# 03_Schematic.net
KiCad netlist of a schematic drawn in Altium Designer
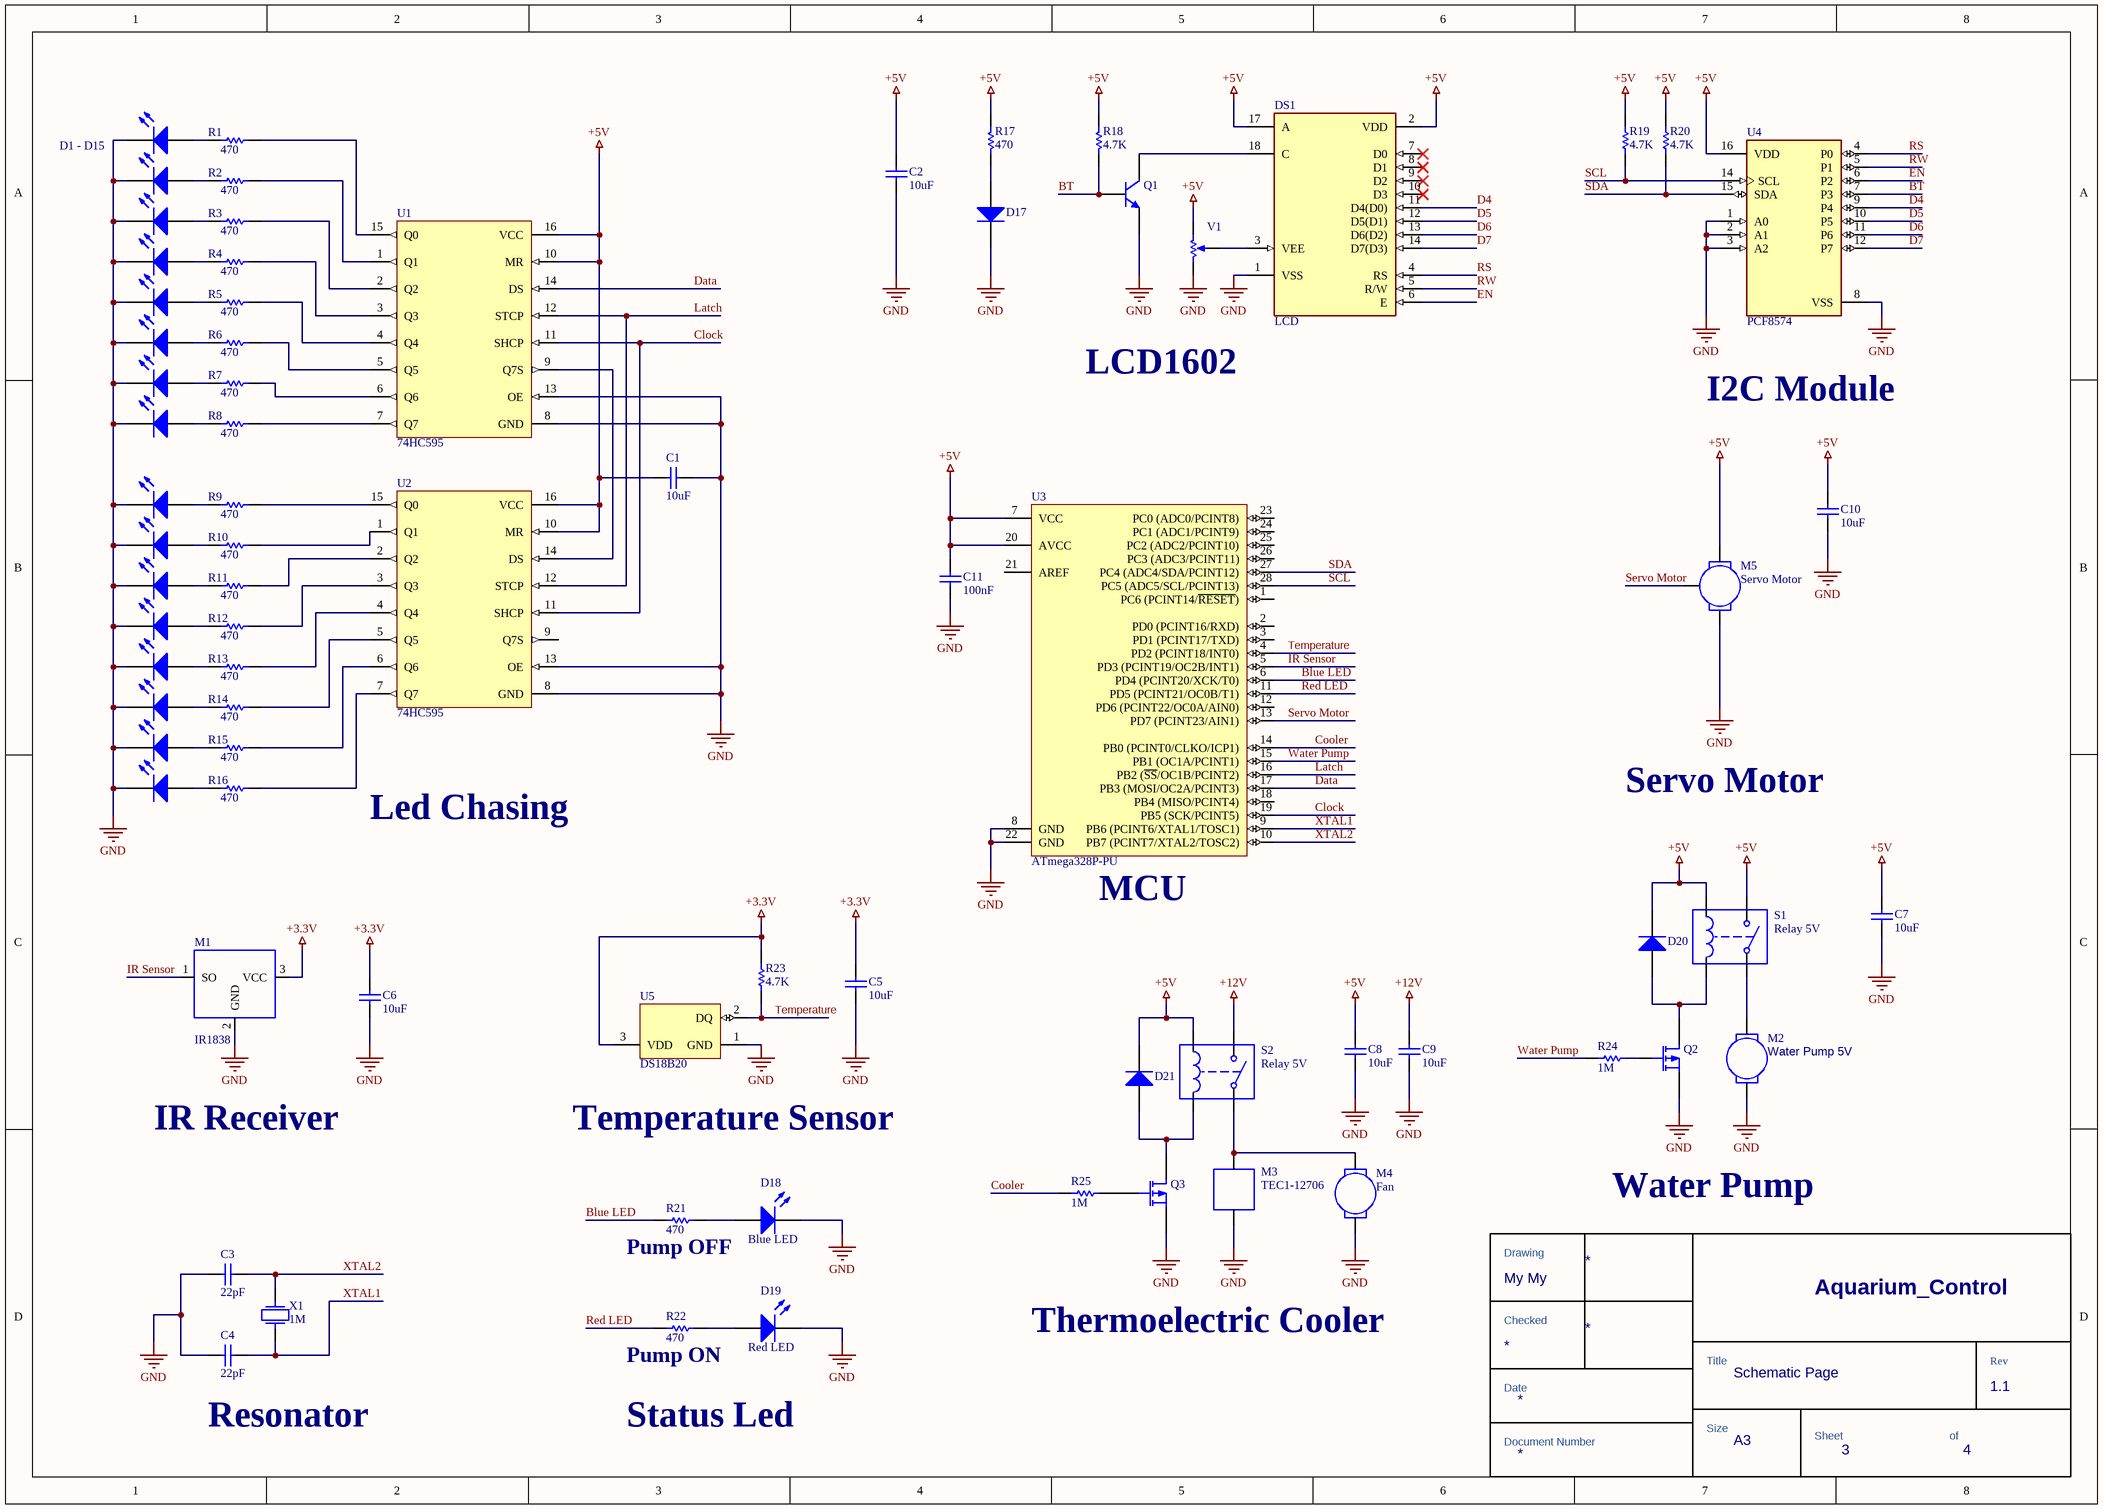
[diagram p0: 03.Schematic.SchDoc]

(export (version "E")
  (design (tool "Eeschema 10.0.6"))
  (components
    (comp (ref "*")
      (value "TitleBlock")
      (description "Common Title Block")
      (libsource (lib "Aquarium_Control") (part "TitleBlock"))
    )
    (comp (ref "C1")
      (value "10uF")
      (description "Capacitor")
      (libsource (lib "Simulation Generic Components") (part "Capacitor"))
    )
    (comp (ref "C2")
      (value "10uF")
      (description "Capacitor")
      (libsource (lib "Simulation Generic Components") (part "Capacitor"))
    )
    (comp (ref "C3")
      (value "22pF")
      (description "Capacitor")
      (libsource (lib "Simulation Generic Components") (part "Capacitor"))
    )
    (comp (ref "C4")
      (value "22pF")
      (description "Capacitor")
      (libsource (lib "Simulation Generic Components") (part "Capacitor"))
    )
    (comp (ref "C5")
      (value "10uF")
      (description "Capacitor")
      (libsource (lib "Simulation Generic Components") (part "Capacitor"))
    )
    (comp (ref "C6")
      (value "10uF")
      (description "Capacitor")
      (libsource (lib "Simulation Generic Components") (part "Capacitor"))
    )
    (comp (ref "C7")
      (value "10uF")
      (description "Capacitor")
      (libsource (lib "Simulation Generic Components") (part "Capacitor"))
    )
    (comp (ref "C8")
      (value "10uF")
      (description "Capacitor")
      (libsource (lib "Simulation Generic Components") (part "Capacitor"))
    )
    (comp (ref "C9")
      (value "10uF")
      (description "Capacitor")
      (libsource (lib "Simulation Generic Components") (part "Capacitor"))
    )
    (comp (ref "C10")
      (value "10uF")
      (description "Capacitor")
      (libsource (lib "Simulation Generic Components") (part "Capacitor"))
    )
    (comp (ref "C11")
      (value "100nF")
      (description "Capacitor")
      (libsource (lib "Simulation Generic Components") (part "Capacitor"))
    )
    (comp (ref "D1")
      (value "Light-Emitting Diode")
      (libsource (lib "Simulation Generic Components") (part "LED"))
    )
    (comp (ref "D2")
      (value "Light-Emitting Diode")
      (libsource (lib "Simulation Generic Components") (part "LED"))
    )
    (comp (ref "D3")
      (value "Light-Emitting Diode")
      (libsource (lib "Simulation Generic Components") (part "LED"))
    )
    (comp (ref "D4")
      (value "Light-Emitting Diode")
      (libsource (lib "Simulation Generic Components") (part "LED"))
    )
    (comp (ref "D5")
      (value "Light-Emitting Diode")
      (libsource (lib "Simulation Generic Components") (part "LED"))
    )
    (comp (ref "D6")
      (value "Light-Emitting Diode")
      (libsource (lib "Simulation Generic Components") (part "LED"))
    )
    (comp (ref "D7")
      (value "Light-Emitting Diode")
      (libsource (lib "Simulation Generic Components") (part "LED"))
    )
    (comp (ref "D8")
      (value "Light-Emitting Diode")
      (libsource (lib "Simulation Generic Components") (part "LED"))
    )
    (comp (ref "D9")
      (value "Light-Emitting Diode")
      (libsource (lib "Simulation Generic Components") (part "LED"))
    )
    (comp (ref "D10")
      (value "Light-Emitting Diode")
      (libsource (lib "Simulation Generic Components") (part "LED"))
    )
    (comp (ref "D11")
      (value "Light-Emitting Diode")
      (libsource (lib "Simulation Generic Components") (part "LED"))
    )
    (comp (ref "D12")
      (value "Light-Emitting Diode")
      (libsource (lib "Simulation Generic Components") (part "LED"))
    )
    (comp (ref "D13")
      (value "Light-Emitting Diode")
      (libsource (lib "Simulation Generic Components") (part "LED"))
    )
    (comp (ref "D14")
      (value "Light-Emitting Diode")
      (libsource (lib "Simulation Generic Components") (part "LED"))
    )
    (comp (ref "D15")
      (value "Light-Emitting Diode")
      (libsource (lib "Simulation Generic Components") (part "LED"))
    )
    (comp (ref "D16")
      (value "Light-Emitting Diode")
      (libsource (lib "Simulation Generic Components") (part "LED"))
    )
    (comp (ref "D17") (value "Diode") (libsource (lib "Simulation Generic Components") (part "Diode")))
    (comp (ref "D18")
      (value "Blue LED")
      (description "Light-Emitting Diode")
      (libsource (lib "Simulation Generic Components") (part "LED"))
    )
    (comp (ref "D19")
      (value "Red LED")
      (description "Light-Emitting Diode")
      (libsource (lib "Simulation Generic Components") (part "LED"))
    )
    (comp (ref "D20") (value "Diode") (libsource (lib "Simulation Generic Components") (part "Diode")))
    (comp (ref "D21") (value "Diode") (libsource (lib "Simulation Generic Components") (part "Diode")))
    (comp (ref "DS1")
      (value "LCD")
      (footprint "FP-EA_DIP162-DHNLED-MFG")
      (description "LCD MOD CHAR 2X16 Y/G BACKLIT")
      (fields
        (field (name "MANUFACTURER PART NUMBER") "EA DIP162-DHNLED")
        (field (name "MANUFACTURER") "Display Visions")
      )
      (libsource (lib "Altium Content Vault") (part "d15ad439837a3ed901fb7cfc26901aa"))
    )
    (comp (ref "M1") (value "IR1838") (libsource (lib "Aquarium_Control") (part "IR1838")))
    (comp (ref "M2")
      (value "Water Pump 5V")
      (description "DC Motor")
      (libsource (lib "Aquarium_Control_1") (part "DC Motor"))
    )
    (comp (ref "M3") (value "TEC1-12706") (libsource (lib "Aquarium_Control") (part "TEC1-12706")))
    (comp (ref "M4") (value "Fan") (libsource (lib "Aquarium_Control") (part "Fan")))
    (comp (ref "M5") (value "Servo Motor") (libsource (lib "Aquarium_Control") (part "Servo Motor")))
    (comp (ref "Q1")
      (value "Bipolar NPN 3 Pins Transistor VBIC Model")
      (libsource (lib "Simulation Generic Components") (part "BJT NPN VBIC"))
    )
    (comp (ref "Q2")
      (value "P-channel Power MOSFET VDMOS Model")
      (libsource (lib "Simulation Generic Components") (part "MOSFET P-ch VDMOS"))
    )
    (comp (ref "Q3")
      (value "P-channel Power MOSFET VDMOS Model")
      (libsource (lib "Simulation Generic Components") (part "MOSFET P-ch VDMOS"))
    )
    (comp (ref "R1")
      (value "470")
      (description "Resistor")
      (libsource (lib "Simulation Generic Components") (part "Resistor"))
    )
    (comp (ref "R2")
      (value "470")
      (description "Resistor")
      (libsource (lib "Simulation Generic Components") (part "Resistor"))
    )
    (comp (ref "R3")
      (value "470")
      (description "Resistor")
      (libsource (lib "Simulation Generic Components") (part "Resistor"))
    )
    (comp (ref "R4")
      (value "470")
      (description "Resistor")
      (libsource (lib "Simulation Generic Components") (part "Resistor"))
    )
    (comp (ref "R5")
      (value "470")
      (description "Resistor")
      (libsource (lib "Simulation Generic Components") (part "Resistor"))
    )
    (comp (ref "R6")
      (value "470")
      (description "Resistor")
      (libsource (lib "Simulation Generic Components") (part "Resistor"))
    )
    (comp (ref "R7")
      (value "470")
      (description "Resistor")
      (libsource (lib "Simulation Generic Components") (part "Resistor"))
    )
    (comp (ref "R8")
      (value "470")
      (description "Resistor")
      (libsource (lib "Simulation Generic Components") (part "Resistor"))
    )
    (comp (ref "R9")
      (value "470")
      (description "Resistor")
      (libsource (lib "Simulation Generic Components") (part "Resistor"))
    )
    (comp (ref "R10")
      (value "470")
      (description "Resistor")
      (libsource (lib "Simulation Generic Components") (part "Resistor"))
    )
    (comp (ref "R11")
      (value "470")
      (description "Resistor")
      (libsource (lib "Simulation Generic Components") (part "Resistor"))
    )
    (comp (ref "R12")
      (value "470")
      (description "Resistor")
      (libsource (lib "Simulation Generic Components") (part "Resistor"))
    )
    (comp (ref "R13")
      (value "470")
      (description "Resistor")
      (libsource (lib "Simulation Generic Components") (part "Resistor"))
    )
    (comp (ref "R14")
      (value "470")
      (description "Resistor")
      (libsource (lib "Simulation Generic Components") (part "Resistor"))
    )
    (comp (ref "R15")
      (value "470")
      (description "Resistor")
      (libsource (lib "Simulation Generic Components") (part "Resistor"))
    )
    (comp (ref "R16")
      (value "470")
      (description "Resistor")
      (libsource (lib "Simulation Generic Components") (part "Resistor"))
    )
    (comp (ref "R17")
      (value "470")
      (description "Resistor")
      (libsource (lib "Simulation Generic Components") (part "Resistor"))
    )
    (comp (ref "R18")
      (value "4.7K")
      (description "Resistor")
      (libsource (lib "Simulation Generic Components") (part "Resistor"))
    )
    (comp (ref "R19")
      (value "4.7K")
      (description "Resistor")
      (libsource (lib "Simulation Generic Components") (part "Resistor"))
    )
    (comp (ref "R20")
      (value "4.7K")
      (description "Resistor")
      (libsource (lib "Simulation Generic Components") (part "Resistor"))
    )
    (comp (ref "R21")
      (value "470")
      (description "Resistor")
      (libsource (lib "Simulation Generic Components") (part "Resistor"))
    )
    (comp (ref "R22")
      (value "470")
      (description "Resistor")
      (libsource (lib "Simulation Generic Components") (part "Resistor"))
    )
    (comp (ref "R23")
      (value "4.7K")
      (description "Resistor")
      (libsource (lib "Simulation Generic Components") (part "Resistor"))
    )
    (comp (ref "R24")
      (value "1M")
      (description "Resistor")
      (libsource (lib "Simulation Generic Components") (part "Resistor"))
    )
    (comp (ref "R25")
      (value "1M")
      (description "Resistor")
      (libsource (lib "Simulation Generic Components") (part "Resistor"))
    )
    (comp (ref "S1")
      (value "Relay 5V")
      (description "Single-Pole, Single-Throw Normally Opened Relay")
      (libsource (lib "Simulation Generic Components") (part "SPST Relay NO"))
    )
    (comp (ref "S2")
      (value "Single-Pole, Single-Throw Normally Opened Relay")
      (libsource (lib "Simulation Generic Components") (part "SPST Relay NO"))
    )
    (comp (ref "U1") (value "74HC595") (libsource (lib "Aquarium_Control") (part "74HC595")))
    (comp (ref "U2") (value "74HC595") (libsource (lib "Aquarium_Control") (part "74HC595")))
    (comp (ref "U3")
      (value "ATmega328P-PU")
      (footprint "28P3")
      (libsource (lib "Altium Content Vault") (part "MC-8B-ATM48-IL28"))
    )
    (comp (ref "U4")
      (value "PCF8574")
      (footprint "FP-SOT162-1-MFG")
      (description "IC I/O EXPANDER I2C 8B 16SOIC")
      (fields
        (field (name "MANUFACTURER PART NUMBER") "PCF8574T/3,518")
        (field (name "MANUFACTURER") "NXP Semiconductors")
      )
      (libsource (lib "Altium Content Vault") (part "f7fde53ce59de981fb0b266a4e103eb"))
    )
    (comp (ref "U5")
      (value "DS18B20")
      (footprint "Q3+1")
      (libsource (lib "Altium Content Vault") (part "SEN-TEMP-DS1821-SIL3"))
    )
    (comp (ref "V1")
      (value "Potentiometer")
      (libsource (lib "Simulation Generic Components") (part "Potentiometer"))
    )
    (comp (ref "X1")
      (value "Crystal")
      (fields (field (name "F0") "1M"))
      (libsource (lib "Simulation Generic Components") (part "Crystal"))
    )
  )
  (nets
    (net (code "1") (name "+3.3V") (class "Default")
      (node (ref "C5") (pin "2") (pinfunction "2_2") (pintype "passive"))
      (node (ref "C6") (pin "2") (pinfunction "2_2") (pintype "passive"))
      (node (ref "M1") (pin "3") (pinfunction "VCC_3") (pintype "passive"))
      (node (ref "R23") (pin "2") (pinfunction "2_2") (pintype "passive"))
      (node (ref "U5") (pin "3") (pinfunction "VDD_3") (pintype "power_in"))
    )
    (net (code "2") (name "+5V") (class "Default")
      (node (ref "C1") (pin "1") (pinfunction "1_1") (pintype "passive"))
      (node (ref "C10") (pin "2") (pinfunction "2_2") (pintype "passive"))
      (node (ref "C11") (pin "2") (pinfunction "2_2") (pintype "passive"))
      (node (ref "C2") (pin "2") (pinfunction "2_2") (pintype "passive"))
      (node (ref "C7") (pin "2") (pinfunction "2_2") (pintype "passive"))
      (node (ref "C8") (pin "2") (pinfunction "2_2") (pintype "passive"))
      (node (ref "D20") (pin "2") (pinfunction "K_2") (pintype "passive"))
      (node (ref "D21") (pin "2") (pinfunction "K_2") (pintype "passive"))
      (node (ref "DS1") (pin "17") (pinfunction "A_17") (pintype "passive"))
      (node (ref "DS1") (pin "2") (pinfunction "VDD_2") (pintype "power_in"))
      (node (ref "M5") (pin "1") (pinfunction "1_1") (pintype "passive"))
      (node (ref "R17") (pin "2") (pinfunction "2_2") (pintype "passive"))
      (node (ref "R18") (pin "2") (pinfunction "2_2") (pintype "passive"))
      (node (ref "R19") (pin "2") (pinfunction "2_2") (pintype "passive"))
      (node (ref "R20") (pin "2") (pinfunction "2_2") (pintype "passive"))
      (node (ref "S1") (pin "2") (pinfunction "2_2") (pintype "passive"))
      (node (ref "S1") (pin "4") (pinfunction "4_4") (pintype "passive"))
      (node (ref "S2") (pin "4") (pinfunction "4_4") (pintype "passive"))
      (node (ref "U1") (pin "10") (pinfunction "MR_10") (pintype "input"))
      (node (ref "U1") (pin "16") (pinfunction "VCC_16") (pintype "passive"))
      (node (ref "U2") (pin "10") (pinfunction "MR_10") (pintype "input"))
      (node (ref "U2") (pin "16") (pinfunction "VCC_16") (pintype "passive"))
      (node (ref "U3") (pin "20") (pinfunction "AVCC_20") (pintype "power_in"))
      (node (ref "U3") (pin "7") (pinfunction "VCC_7") (pintype "power_in"))
      (node (ref "U4") (pin "16") (pinfunction "VDD_16") (pintype "power_in"))
      (node (ref "V1") (pin "1") (pinfunction "TOP_1") (pintype "passive"))
    )
    (net (code "3") (name "+12V") (class "Default")
      (node (ref "C9") (pin "2") (pinfunction "2_2") (pintype "passive"))
      (node (ref "S2") (pin "2") (pinfunction "2_2") (pintype "passive"))
    )
    (net (code "4") (name "/BT") (class "Default")
      (node (ref "Q1") (pin "2") (pinfunction "B_2") (pintype "passive"))
      (node (ref "R18") (pin "1") (pinfunction "1_1") (pintype "passive"))
      (node (ref "U4") (pin "7") (pinfunction "P3_7") (pintype "bidirectional"))
    )
    (net (code "5") (name "/Blue LED") (class "Default")
      (node (ref "R21") (pin "1") (pinfunction "1_1") (pintype "passive"))
      (node (ref "U3") (pin "6") (pinfunction "PD4_(PCINT20/XCK/T0)_6") (pintype "bidirectional"))
    )
    (net (code "6") (name "/Clock") (class "Default")
      (node (ref "U1") (pin "11") (pinfunction "SHCP_11") (pintype "input"))
      (node (ref "U2") (pin "11") (pinfunction "SHCP_11") (pintype "input"))
      (node (ref "U3") (pin "19") (pinfunction "PB5_(SCK/PCINT5)_19") (pintype "bidirectional"))
    )
    (net (code "7") (name "/Cooler") (class "Default")
      (node (ref "R25") (pin "1") (pinfunction "1_1") (pintype "passive"))
      (node (ref "U3") (pin "14") (pinfunction "PB0_(PCINT0/CLKO/ICP1)_14") (pintype "bidirectional"))
    )
    (net (code "8") (name "/D4") (class "Default")
      (node (ref "DS1") (pin "11") (pinfunction "D4(D0)_11") (pintype "input"))
      (node (ref "U4") (pin "9") (pinfunction "P4_9") (pintype "bidirectional"))
    )
    (net (code "9") (name "/D5") (class "Default")
      (node (ref "DS1") (pin "12") (pinfunction "D5(D1)_12") (pintype "input"))
      (node (ref "U4") (pin "10") (pinfunction "P5_10") (pintype "bidirectional"))
    )
    (net (code "10") (name "/D6") (class "Default")
      (node (ref "DS1") (pin "13") (pinfunction "D6(D2)_13") (pintype "input"))
      (node (ref "U4") (pin "11") (pinfunction "P6_11") (pintype "bidirectional"))
    )
    (net (code "11") (name "/D7") (class "Default")
      (node (ref "DS1") (pin "14") (pinfunction "D7(D3)_14") (pintype "input"))
      (node (ref "U4") (pin "12") (pinfunction "P7_12") (pintype "bidirectional"))
    )
    (net (code "12") (name "/Data") (class "Default")
      (node (ref "U1") (pin "14") (pinfunction "DS_14") (pintype "input"))
      (node (ref "U3") (pin "17") (pinfunction "PB3_(MOSI/OC2A/PCINT3)_17") (pintype "bidirectional"))
    )
    (net (code "13") (name "/EN") (class "Default")
      (node (ref "DS1") (pin "6") (pinfunction "E_6") (pintype "input"))
      (node (ref "U4") (pin "6") (pinfunction "P2_6") (pintype "bidirectional"))
    )
    (net (code "14") (name "/IR Sensor") (class "Default")
      (node (ref "M1") (pin "1") (pinfunction "SO_1") (pintype "passive"))
      (node (ref "U3") (pin "5") (pinfunction "PD3_(PCINT19/OC2B/INT1)_5") (pintype "bidirectional"))
    )
    (net (code "15") (name "/Latch") (class "Default")
      (node (ref "U1") (pin "12") (pinfunction "STCP_12") (pintype "input"))
      (node (ref "U2") (pin "12") (pinfunction "STCP_12") (pintype "input"))
      (node (ref "U3") (pin "16") (pinfunction "PB2_(~{SS}/OC1B/PCINT2)_16") (pintype "bidirectional"))
    )
    (net (code "16") (name "/RS") (class "Default")
      (node (ref "DS1") (pin "4") (pinfunction "RS_4") (pintype "input"))
      (node (ref "U4") (pin "4") (pinfunction "P0_4") (pintype "bidirectional"))
    )
    (net (code "17") (name "/RW") (class "Default")
      (node (ref "DS1") (pin "5") (pinfunction "R/W_5") (pintype "input"))
      (node (ref "U4") (pin "5") (pinfunction "P1_5") (pintype "bidirectional"))
    )
    (net (code "18") (name "/Red LED") (class "Default")
      (node (ref "R22") (pin "1") (pinfunction "1_1") (pintype "passive"))
      (node (ref "U3") (pin "11") (pinfunction "PD5_(PCINT21/OC0B/T1)_11") (pintype "bidirectional"))
    )
    (net (code "19") (name "/SCL") (class "Default")
      (node (ref "R19") (pin "1") (pinfunction "1_1") (pintype "passive"))
      (node (ref "U3") (pin "28") (pinfunction "PC5_(ADC5/SCL/PCINT13)_28") (pintype "bidirectional"))
      (node (ref "U4") (pin "14") (pinfunction "SCL_14") (pintype "input"))
    )
    (net (code "20") (name "/SDA") (class "Default")
      (node (ref "R20") (pin "1") (pinfunction "1_1") (pintype "passive"))
      (node (ref "U3") (pin "27") (pinfunction "PC4_(ADC4/SDA/PCINT12)_27") (pintype "bidirectional"))
      (node (ref "U4") (pin "15") (pinfunction "SDA_15") (pintype "bidirectional"))
    )
    (net (code "21") (name "/Servo Motor") (class "Default")
      (node (ref "M5") (pin "1") (pinfunction "1_1") (pintype "passive"))
      (node (ref "U3") (pin "13") (pinfunction "PD7_(PCINT23/AIN1)_13") (pintype "bidirectional"))
    )
    (net (code "22") (name "/Temperature") (class "Default")
      (node (ref "R23") (pin "1") (pinfunction "1_1") (pintype "passive"))
      (node (ref "U3") (pin "4") (pinfunction "PD2_(PCINT18/INT0)_4") (pintype "bidirectional"))
      (node (ref "U5") (pin "2") (pinfunction "DQ_2") (pintype "bidirectional"))
    )
    (net (code "23") (name "/Water Pump") (class "Default")
      (node (ref "R24") (pin "1") (pinfunction "1_1") (pintype "passive"))
      (node (ref "U3") (pin "15") (pinfunction "PB1_(OC1A/PCINT1)_15") (pintype "bidirectional"))
    )
    (net (code "24") (name "/XTAL1") (class "Default")
      (node (ref "C4") (pin "2") (pinfunction "2_2") (pintype "passive"))
      (node (ref "U3") (pin "9") (pinfunction "PB6_(PCINT6/XTAL1/TOSC1)_9") (pintype "bidirectional"))
      (node (ref "X1") (pin "1") (pinfunction "1_1") (pintype "passive"))
    )
    (net (code "25") (name "/XTAL2") (class "Default")
      (node (ref "C3") (pin "2") (pinfunction "2_2") (pintype "passive"))
      (node (ref "U3") (pin "10") (pinfunction "PB7_(PCINT7/XTAL2/TOSC2)_10") (pintype "bidirectional"))
      (node (ref "X1") (pin "2") (pinfunction "2_2") (pintype "passive"))
    )
    (net (code "26") (name "GND") (class "Default")
      (node (ref "C1") (pin "2") (pinfunction "2_2") (pintype "passive"))
      (node (ref "C10") (pin "1") (pinfunction "1_1") (pintype "passive"))
      (node (ref "C11") (pin "1") (pinfunction "1_1") (pintype "passive"))
      (node (ref "C2") (pin "1") (pinfunction "1_1") (pintype "passive"))
      (node (ref "C3") (pin "1") (pinfunction "1_1") (pintype "passive"))
      (node (ref "C4") (pin "1") (pinfunction "1_1") (pintype "passive"))
      (node (ref "C5") (pin "1") (pinfunction "1_1") (pintype "passive"))
      (node (ref "C6") (pin "1") (pinfunction "1_1") (pintype "passive"))
      (node (ref "C7") (pin "1") (pinfunction "1_1") (pintype "passive"))
      (node (ref "C8") (pin "1") (pinfunction "1_1") (pintype "passive"))
      (node (ref "C9") (pin "1") (pinfunction "1_1") (pintype "passive"))
      (node (ref "D1") (pin "2") (pinfunction "K_2") (pintype "passive"))
      (node (ref "D10") (pin "2") (pinfunction "K_2") (pintype "passive"))
      (node (ref "D11") (pin "2") (pinfunction "K_2") (pintype "passive"))
      (node (ref "D12") (pin "2") (pinfunction "K_2") (pintype "passive"))
      (node (ref "D13") (pin "2") (pinfunction "K_2") (pintype "passive"))
      (node (ref "D14") (pin "2") (pinfunction "K_2") (pintype "passive"))
      (node (ref "D15") (pin "2") (pinfunction "K_2") (pintype "passive"))
      (node (ref "D16") (pin "2") (pinfunction "K_2") (pintype "passive"))
      (node (ref "D17") (pin "2") (pinfunction "K_2") (pintype "passive"))
      (node (ref "D18") (pin "2") (pinfunction "K_2") (pintype "passive"))
      (node (ref "D19") (pin "2") (pinfunction "K_2") (pintype "passive"))
      (node (ref "D2") (pin "2") (pinfunction "K_2") (pintype "passive"))
      (node (ref "D3") (pin "2") (pinfunction "K_2") (pintype "passive"))
      (node (ref "D4") (pin "2") (pinfunction "K_2") (pintype "passive"))
      (node (ref "D5") (pin "2") (pinfunction "K_2") (pintype "passive"))
      (node (ref "D6") (pin "2") (pinfunction "K_2") (pintype "passive"))
      (node (ref "D7") (pin "2") (pinfunction "K_2") (pintype "passive"))
      (node (ref "D8") (pin "2") (pinfunction "K_2") (pintype "passive"))
      (node (ref "D9") (pin "2") (pinfunction "K_2") (pintype "passive"))
      (node (ref "DS1") (pin "1") (pinfunction "VSS_1") (pintype "power_in"))
      (node (ref "M1") (pin "2") (pinfunction "GND_2") (pintype "passive"))
      (node (ref "M2") (pin "2") (pinfunction "2_2") (pintype "passive"))
      (node (ref "M3") (pin "2") (pinfunction "2_2") (pintype "passive"))
      (node (ref "M4") (pin "2") (pinfunction "2_2") (pintype "passive"))
      (node (ref "M5") (pin "1") (pinfunction "1_1") (pintype "passive"))
      (node (ref "Q1") (pin "3") (pinfunction "E_3") (pintype "passive"))
      (node (ref "Q2") (pin "3") (pinfunction "S_3") (pintype "passive"))
      (node (ref "Q3") (pin "3") (pinfunction "S_3") (pintype "passive"))
      (node (ref "U1") (pin "13") (pinfunction "OE_13") (pintype "input"))
      (node (ref "U1") (pin "8") (pinfunction "GND_8") (pintype "passive"))
      (node (ref "U2") (pin "13") (pinfunction "OE_13") (pintype "input"))
      (node (ref "U2") (pin "8") (pinfunction "GND_8") (pintype "passive"))
      (node (ref "U3") (pin "22") (pinfunction "GND_22") (pintype "power_in"))
      (node (ref "U3") (pin "8") (pinfunction "GND_8") (pintype "power_in"))
      (node (ref "U4") (pin "1") (pinfunction "A0_1") (pintype "input"))
      (node (ref "U4") (pin "2") (pinfunction "A1_2") (pintype "input"))
      (node (ref "U4") (pin "3") (pinfunction "A2_3") (pintype "input"))
      (node (ref "U4") (pin "8") (pinfunction "VSS_8") (pintype "power_in"))
      (node (ref "U5") (pin "1") (pinfunction "GND_1") (pintype "power_in"))
      (node (ref "V1") (pin "2") (pinfunction "BOT_2") (pintype "passive"))
    )
    (net (code "27") (name "Net-(D1-A)") (class "Default")
      (node (ref "D1") (pin "1") (pinfunction "A_1") (pintype "passive"))
      (node (ref "R1") (pin "2") (pinfunction "2_2") (pintype "passive"))
    )
    (net (code "28") (name "Net-(D2-A)") (class "Default")
      (node (ref "D2") (pin "1") (pinfunction "A_1") (pintype "passive"))
      (node (ref "R2") (pin "2") (pinfunction "2_2") (pintype "passive"))
    )
    (net (code "29") (name "Net-(D3-A)") (class "Default")
      (node (ref "D3") (pin "1") (pinfunction "A_1") (pintype "passive"))
      (node (ref "R3") (pin "2") (pinfunction "2_2") (pintype "passive"))
    )
    (net (code "30") (name "Net-(D4-A)") (class "Default")
      (node (ref "D4") (pin "1") (pinfunction "A_1") (pintype "passive"))
      (node (ref "R4") (pin "2") (pinfunction "2_2") (pintype "passive"))
    )
    (net (code "31") (name "Net-(D5-A)") (class "Default")
      (node (ref "D5") (pin "1") (pinfunction "A_1") (pintype "passive"))
      (node (ref "R5") (pin "2") (pinfunction "2_2") (pintype "passive"))
    )
    (net (code "32") (name "Net-(D6-A)") (class "Default")
      (node (ref "D6") (pin "1") (pinfunction "A_1") (pintype "passive"))
      (node (ref "R6") (pin "2") (pinfunction "2_2") (pintype "passive"))
    )
    (net (code "33") (name "Net-(D7-A)") (class "Default")
      (node (ref "D7") (pin "1") (pinfunction "A_1") (pintype "passive"))
      (node (ref "R7") (pin "2") (pinfunction "2_2") (pintype "passive"))
    )
    (net (code "34") (name "Net-(D8-A)") (class "Default")
      (node (ref "D8") (pin "1") (pinfunction "A_1") (pintype "passive"))
      (node (ref "R8") (pin "2") (pinfunction "2_2") (pintype "passive"))
    )
    (net (code "35") (name "Net-(D9-A)") (class "Default")
      (node (ref "D9") (pin "1") (pinfunction "A_1") (pintype "passive"))
      (node (ref "R9") (pin "2") (pinfunction "2_2") (pintype "passive"))
    )
    (net (code "36") (name "Net-(D10-A)") (class "Default")
      (node (ref "D10") (pin "1") (pinfunction "A_1") (pintype "passive"))
      (node (ref "R10") (pin "2") (pinfunction "2_2") (pintype "passive"))
    )
    (net (code "37") (name "Net-(D11-A)") (class "Default")
      (node (ref "D11") (pin "1") (pinfunction "A_1") (pintype "passive"))
      (node (ref "R11") (pin "2") (pinfunction "2_2") (pintype "passive"))
    )
    (net (code "38") (name "Net-(D12-A)") (class "Default")
      (node (ref "D12") (pin "1") (pinfunction "A_1") (pintype "passive"))
      (node (ref "R12") (pin "2") (pinfunction "2_2") (pintype "passive"))
    )
    (net (code "39") (name "Net-(D13-A)") (class "Default")
      (node (ref "D13") (pin "1") (pinfunction "A_1") (pintype "passive"))
      (node (ref "R13") (pin "2") (pinfunction "2_2") (pintype "passive"))
    )
    (net (code "40") (name "Net-(D14-A)") (class "Default")
      (node (ref "D14") (pin "1") (pinfunction "A_1") (pintype "passive"))
      (node (ref "R14") (pin "2") (pinfunction "2_2") (pintype "passive"))
    )
    (net (code "41") (name "Net-(D15-A)") (class "Default")
      (node (ref "D15") (pin "1") (pinfunction "A_1") (pintype "passive"))
      (node (ref "R15") (pin "2") (pinfunction "2_2") (pintype "passive"))
    )
    (net (code "42") (name "Net-(D16-A)") (class "Default")
      (node (ref "D16") (pin "1") (pinfunction "A_1") (pintype "passive"))
      (node (ref "R16") (pin "2") (pinfunction "2_2") (pintype "passive"))
    )
    (net (code "43") (name "Net-(D17-A)") (class "Default")
      (node (ref "D17") (pin "1") (pinfunction "A_1") (pintype "passive"))
      (node (ref "R17") (pin "1") (pinfunction "1_1") (pintype "passive"))
    )
    (net (code "44") (name "Net-(D18-A)") (class "Default")
      (node (ref "D18") (pin "1") (pinfunction "A_1") (pintype "passive"))
      (node (ref "R21") (pin "2") (pinfunction "2_2") (pintype "passive"))
    )
    (net (code "45") (name "Net-(D19-A)") (class "Default")
      (node (ref "D19") (pin "1") (pinfunction "A_1") (pintype "passive"))
      (node (ref "R22") (pin "2") (pinfunction "2_2") (pintype "passive"))
    )
    (net (code "46") (name "Net-(D20-A)") (class "Default")
      (node (ref "D20") (pin "1") (pinfunction "A_1") (pintype "passive"))
      (node (ref "Q2") (pin "1") (pinfunction "D_1") (pintype "passive"))
      (node (ref "S1") (pin "3") (pinfunction "3_3") (pintype "passive"))
    )
    (net (code "47") (name "Net-(D21-A)") (class "Default")
      (node (ref "D21") (pin "1") (pinfunction "A_1") (pintype "passive"))
      (node (ref "Q3") (pin "1") (pinfunction "D_1") (pintype "passive"))
      (node (ref "S2") (pin "3") (pinfunction "3_3") (pintype "passive"))
    )
    (net (code "48") (name "Net-(DS1-C)") (class "Default")
      (node (ref "DS1") (pin "18") (pinfunction "C_18") (pintype "passive"))
      (node (ref "Q1") (pin "1") (pinfunction "C_1") (pintype "passive"))
    )
    (net (code "49") (name "Net-(DS1-VEE)") (class "Default")
      (node (ref "DS1") (pin "3") (pinfunction "VEE_3") (pintype "input"))
      (node (ref "V1") (pin "3") (pinfunction "TAP_3") (pintype "passive"))
    )
    (net (code "50") (name "Net-(M2-Pad1)") (class "Default")
      (node (ref "M2") (pin "1") (pinfunction "1_1") (pintype "passive"))
      (node (ref "S1") (pin "1") (pinfunction "1_1") (pintype "passive"))
    )
    (net (code "51") (name "Net-(M3-Pad1)") (class "Default")
      (node (ref "M3") (pin "1") (pinfunction "1_1") (pintype "passive"))
      (node (ref "M4") (pin "1") (pinfunction "1_1") (pintype "passive"))
      (node (ref "S2") (pin "1") (pinfunction "1_1") (pintype "passive"))
    )
    (net (code "52") (name "Net-(Q2-G)") (class "Default")
      (node (ref "Q2") (pin "2") (pinfunction "G_2") (pintype "passive"))
      (node (ref "R24") (pin "2") (pinfunction "2_2") (pintype "passive"))
    )
    (net (code "53") (name "Net-(Q3-G)") (class "Default")
      (node (ref "Q3") (pin "2") (pinfunction "G_2") (pintype "passive"))
      (node (ref "R25") (pin "2") (pinfunction "2_2") (pintype "passive"))
    )
    (net (code "54") (name "Net-(U1-Q0)") (class "Default")
      (node (ref "R1") (pin "1") (pinfunction "1_1") (pintype "passive"))
      (node (ref "U1") (pin "15") (pinfunction "Q0_15") (pintype "output"))
    )
    (net (code "55") (name "Net-(U1-Q1)") (class "Default")
      (node (ref "R2") (pin "1") (pinfunction "1_1") (pintype "passive"))
      (node (ref "U1") (pin "1") (pinfunction "Q1_1") (pintype "output"))
    )
    (net (code "56") (name "Net-(U1-Q2)") (class "Default")
      (node (ref "R3") (pin "1") (pinfunction "1_1") (pintype "passive"))
      (node (ref "U1") (pin "2") (pinfunction "Q2_2") (pintype "output"))
    )
    (net (code "57") (name "Net-(U1-Q3)") (class "Default")
      (node (ref "R4") (pin "1") (pinfunction "1_1") (pintype "passive"))
      (node (ref "U1") (pin "3") (pinfunction "Q3_3") (pintype "output"))
    )
    (net (code "58") (name "Net-(U1-Q4)") (class "Default")
      (node (ref "R5") (pin "1") (pinfunction "1_1") (pintype "passive"))
      (node (ref "U1") (pin "4") (pinfunction "Q4_4") (pintype "output"))
    )
    (net (code "59") (name "Net-(U1-Q5)") (class "Default")
      (node (ref "R6") (pin "1") (pinfunction "1_1") (pintype "passive"))
      (node (ref "U1") (pin "5") (pinfunction "Q5_5") (pintype "output"))
    )
    (net (code "60") (name "Net-(U1-Q6)") (class "Default")
      (node (ref "R7") (pin "1") (pinfunction "1_1") (pintype "passive"))
      (node (ref "U1") (pin "6") (pinfunction "Q6_6") (pintype "output"))
    )
    (net (code "61") (name "Net-(U1-Q7)") (class "Default")
      (node (ref "R8") (pin "1") (pinfunction "1_1") (pintype "passive"))
      (node (ref "U1") (pin "7") (pinfunction "Q7_7") (pintype "output"))
    )
    (net (code "62") (name "Net-(U1-Q7S)") (class "Default")
      (node (ref "U1") (pin "9") (pinfunction "Q7S_9") (pintype "output"))
      (node (ref "U2") (pin "14") (pinfunction "DS_14") (pintype "input"))
    )
    (net (code "63") (name "Net-(U2-Q0)") (class "Default")
      (node (ref "R9") (pin "1") (pinfunction "1_1") (pintype "passive"))
      (node (ref "U2") (pin "15") (pinfunction "Q0_15") (pintype "output"))
    )
    (net (code "64") (name "Net-(U2-Q1)") (class "Default")
      (node (ref "R10") (pin "1") (pinfunction "1_1") (pintype "passive"))
      (node (ref "U2") (pin "1") (pinfunction "Q1_1") (pintype "output"))
    )
    (net (code "65") (name "Net-(U2-Q2)") (class "Default")
      (node (ref "R11") (pin "1") (pinfunction "1_1") (pintype "passive"))
      (node (ref "U2") (pin "2") (pinfunction "Q2_2") (pintype "output"))
    )
    (net (code "66") (name "Net-(U2-Q3)") (class "Default")
      (node (ref "R12") (pin "1") (pinfunction "1_1") (pintype "passive"))
      (node (ref "U2") (pin "3") (pinfunction "Q3_3") (pintype "output"))
    )
    (net (code "67") (name "Net-(U2-Q4)") (class "Default")
      (node (ref "R13") (pin "1") (pinfunction "1_1") (pintype "passive"))
      (node (ref "U2") (pin "4") (pinfunction "Q4_4") (pintype "output"))
    )
    (net (code "68") (name "Net-(U2-Q5)") (class "Default")
      (node (ref "R14") (pin "1") (pinfunction "1_1") (pintype "passive"))
      (node (ref "U2") (pin "5") (pinfunction "Q5_5") (pintype "output"))
    )
    (net (code "69") (name "Net-(U2-Q6)") (class "Default")
      (node (ref "R15") (pin "1") (pinfunction "1_1") (pintype "passive"))
      (node (ref "U2") (pin "6") (pinfunction "Q6_6") (pintype "output"))
    )
    (net (code "70") (name "Net-(U2-Q7)") (class "Default")
      (node (ref "R16") (pin "1") (pinfunction "1_1") (pintype "passive"))
      (node (ref "U2") (pin "7") (pinfunction "Q7_7") (pintype "output"))
    )
    (net (code "71") (name "unconnected-(DS1-D0-Pad7)") (class "Default")
      (node (ref "DS1") (pin "7") (pinfunction "D0_7") (pintype "input+no_connect"))
    )
    (net (code "72") (name "unconnected-(DS1-D1-Pad8)") (class "Default")
      (node (ref "DS1") (pin "8") (pinfunction "D1_8") (pintype "input+no_connect"))
    )
    (net (code "73") (name "unconnected-(DS1-D2-Pad9)") (class "Default")
      (node (ref "DS1") (pin "9") (pinfunction "D2_9") (pintype "input+no_connect"))
    )
    (net (code "74") (name "unconnected-(DS1-D3-Pad10)") (class "Default")
      (node (ref "DS1") (pin "10") (pinfunction "D3_10") (pintype "input+no_connect"))
    )
    (net (code "75") (name "unconnected-(DS1-NC-Pad15)") (class "Default")
      (node (ref "DS1") (pin "15") (pinfunction "NC_15") (pintype "passive"))
    )
    (net (code "76") (name "unconnected-(DS1-NC-Pad16)") (class "Default")
      (node (ref "DS1") (pin "16") (pinfunction "NC_16") (pintype "passive"))
    )
    (net (code "77") (name "unconnected-(U2-Q7S-Pad9)") (class "Default")
      (node (ref "U2") (pin "9") (pinfunction "Q7S_9") (pintype "output"))
    )
    (net (code "78") (name "unconnected-(U3-AREF-Pad21)") (class "Default")
      (node (ref "U3") (pin "21") (pinfunction "AREF_21") (pintype "power_in"))
    )
    (net (code "79") (name "unconnected-(U3-PB4_(MISO{slash}PCINT4)-Pad18)") (class "Default")
      (node (ref "U3") (pin "18") (pinfunction "PB4_(MISO/PCINT4)_18") (pintype "bidirectional"))
    )
    (net (code "80") (name "unconnected-(U3-PC0_(ADC0{slash}PCINT8)-Pad23)") (class "Default")
      (node (ref "U3") (pin "23") (pinfunction "PC0_(ADC0/PCINT8)_23") (pintype "bidirectional"))
    )
    (net (code "81") (name "unconnected-(U3-PC1_(ADC1{slash}PCINT9)-Pad24)") (class "Default")
      (node (ref "U3") (pin "24") (pinfunction "PC1_(ADC1/PCINT9)_24") (pintype "bidirectional"))
    )
    (net (code "82") (name "unconnected-(U3-PC2_(ADC2{slash}PCINT10)-Pad25)") (class "Default")
      (node (ref "U3") (pin "25") (pinfunction "PC2_(ADC2/PCINT10)_25") (pintype "bidirectional"))
    )
    (net (code "83") (name "unconnected-(U3-PC3_(ADC3{slash}PCINT11)-Pad26)") (class "Default")
      (node (ref "U3") (pin "26") (pinfunction "PC3_(ADC3/PCINT11)_26") (pintype "bidirectional"))
    )
    (net (code "84") (name "unconnected-(U3-PC6_(PCINT14{slash}~{RESET})-Pad1)") (class "Default")
      (node (ref "U3") (pin "1") (pinfunction "PC6_(PCINT14/~{RESET})_1") (pintype "bidirectional"))
    )
    (net (code "85") (name "unconnected-(U3-PD0_(PCINT16{slash}RXD)-Pad2)") (class "Default")
      (node (ref "U3") (pin "2") (pinfunction "PD0_(PCINT16/RXD)_2") (pintype "bidirectional"))
    )
    (net (code "86") (name "unconnected-(U3-PD1_(PCINT17{slash}TXD)-Pad3)") (class "Default")
      (node (ref "U3") (pin "3") (pinfunction "PD1_(PCINT17/TXD)_3") (pintype "bidirectional"))
    )
    (net (code "87") (name "unconnected-(U3-PD6_(PCINT22{slash}OC0A{slash}AIN0)-Pad12)") (class "Default")
      (node (ref "U3") (pin "12") (pinfunction "PD6_(PCINT22/OC0A/AIN0)_12") (pintype "bidirectional"))
    )
    (net (code "88") (name "unconnected-(U4-~{INT}-Pad13)") (class "Default")
      (node (ref "U4") (pin "13") (pinfunction "~{INT}_13") (pintype "open_collector"))
    )
  )
)
